# SCH_HackerCard2_2025-08-10.net
KiCad netlist of a schematic drawn in EasyEDA
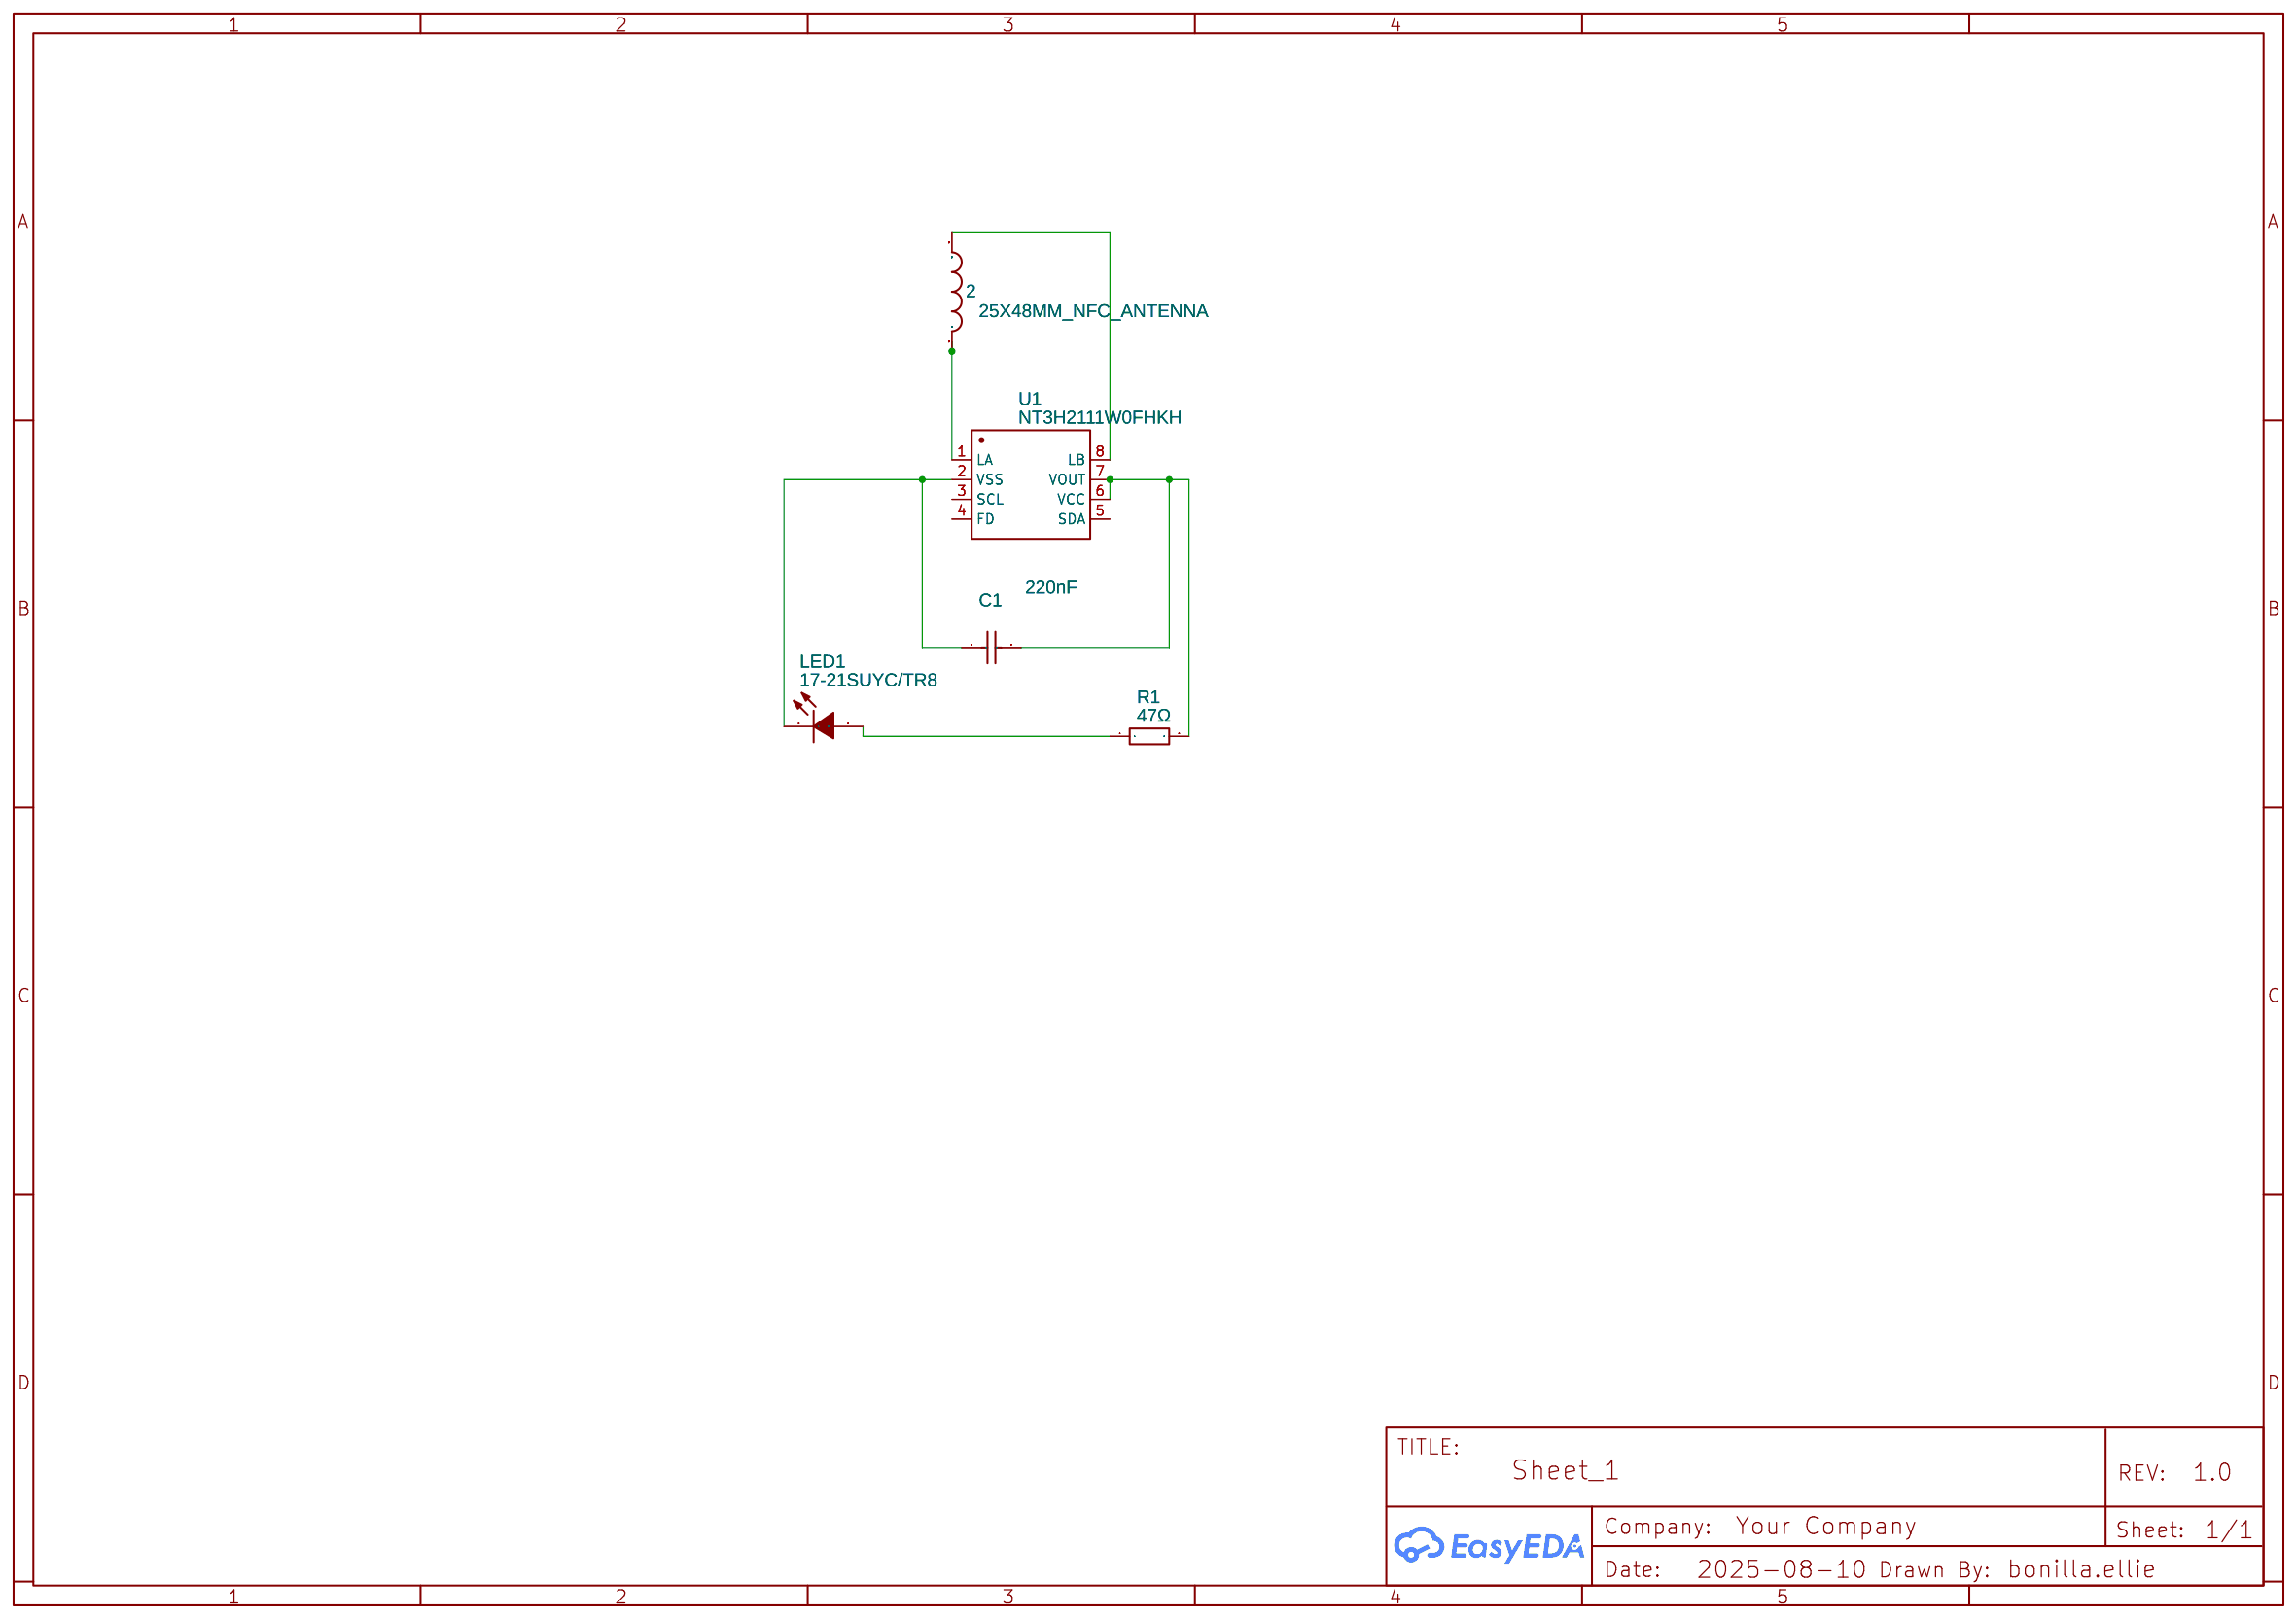
[diagram p0: schematic sheet]

(export (version "E")
  (design (tool "Eeschema 10.0.6"))
  (components
    (comp (ref "2") (value "25X48MM_NFC_ANTENNA") (libsource (lib "") (part "25X48MM_NFC_ANTENNA")))
    (comp (ref "C1")
      (value "220nF")
      (fields
        (field (name "Manufacturer Part") "CL10B224KA8NNNC")
        (field (name "Manufacturer") "SAMSUNG(三星)")
      )
      (libsource (lib "") (part "CL10B224KA8NNNC"))
    )
    (comp (ref "LED1")
      (value "17-21SUYC/TR8")
      (fields (field (name "Manufacturer Part") "KT-0805黄灯") (field (name "Manufacturer") "KENTO"))
      (libsource (lib "") (part "17-21SUYC/TR8"))
    )
    (comp (ref "R1")
      (value "47Ω")
      (fields
        (field (name "Manufacturer Part") "0603WAF470JT5E")
        (field (name "Manufacturer") "UNI-ROYAL(厚声)")
      )
      (libsource (lib "") (part "0603WAF470JT5E"))
    )
    (comp (ref "U1")
      (value "NT3H2111W0FHKH")
      (fields (field (name "Manufacturer") "NXP(恩智浦)"))
      (libsource (lib "") (part "NT3H2111W0FHKH"))
    )
  )
  (nets
    (net (code "1") (name "Net-(LED1-+)") (class "Default")
      (node (ref "LED1") (pin "1") (pinfunction "+_1") (pintype "unspecified"))
      (node (ref "R1") (pin "1") (pinfunction "1_1") (pintype "input"))
    )
    (net (code "2") (name "Net-(LED1--)") (class "Default")
      (node (ref "C1") (pin "1") (pinfunction "1_1") (pintype "input"))
      (node (ref "LED1") (pin "2") (pinfunction "-_2") (pintype "unspecified"))
      (node (ref "U1") (pin "2") (pinfunction "VSS_2") (pintype "unspecified"))
    )
    (net (code "3") (name "Net-(U1-LA)") (class "Default")
      (node (ref "2") (pin "P$2") (pinfunction "P$2_P$2") (pintype "bidirectional"))
      (node (ref "U1") (pin "1") (pinfunction "LA_1") (pintype "unspecified"))
    )
    (net (code "4") (name "Net-(U1-LB)") (class "Default")
      (node (ref "2") (pin "P$1") (pinfunction "P$1_P$1") (pintype "bidirectional"))
      (node (ref "U1") (pin "8") (pinfunction "LB_8") (pintype "unspecified"))
    )
    (net (code "5") (name "Net-(U1-VCC)") (class "Default")
      (node (ref "C1") (pin "2") (pinfunction "2_2") (pintype "input"))
      (node (ref "R1") (pin "2") (pinfunction "2_2") (pintype "input"))
      (node (ref "U1") (pin "6") (pinfunction "VCC_6") (pintype "unspecified"))
      (node (ref "U1") (pin "7") (pinfunction "VOUT_7") (pintype "unspecified"))
    )
    (net (code "6") (name "unconnected-(U1-FD-Pad4)") (class "Default")
      (node (ref "U1") (pin "4") (pinfunction "FD_4") (pintype "unspecified"))
    )
    (net (code "7") (name "unconnected-(U1-SCL-Pad3)") (class "Default")
      (node (ref "U1") (pin "3") (pinfunction "SCL_3") (pintype "unspecified"))
    )
    (net (code "8") (name "unconnected-(U1-SDA-Pad5)") (class "Default")
      (node (ref "U1") (pin "5") (pinfunction "SDA_5") (pintype "unspecified"))
    )
  )
)
